# LMQ644_test_SCH.net
KiCad netlist of a schematic drawn in Altium Designer
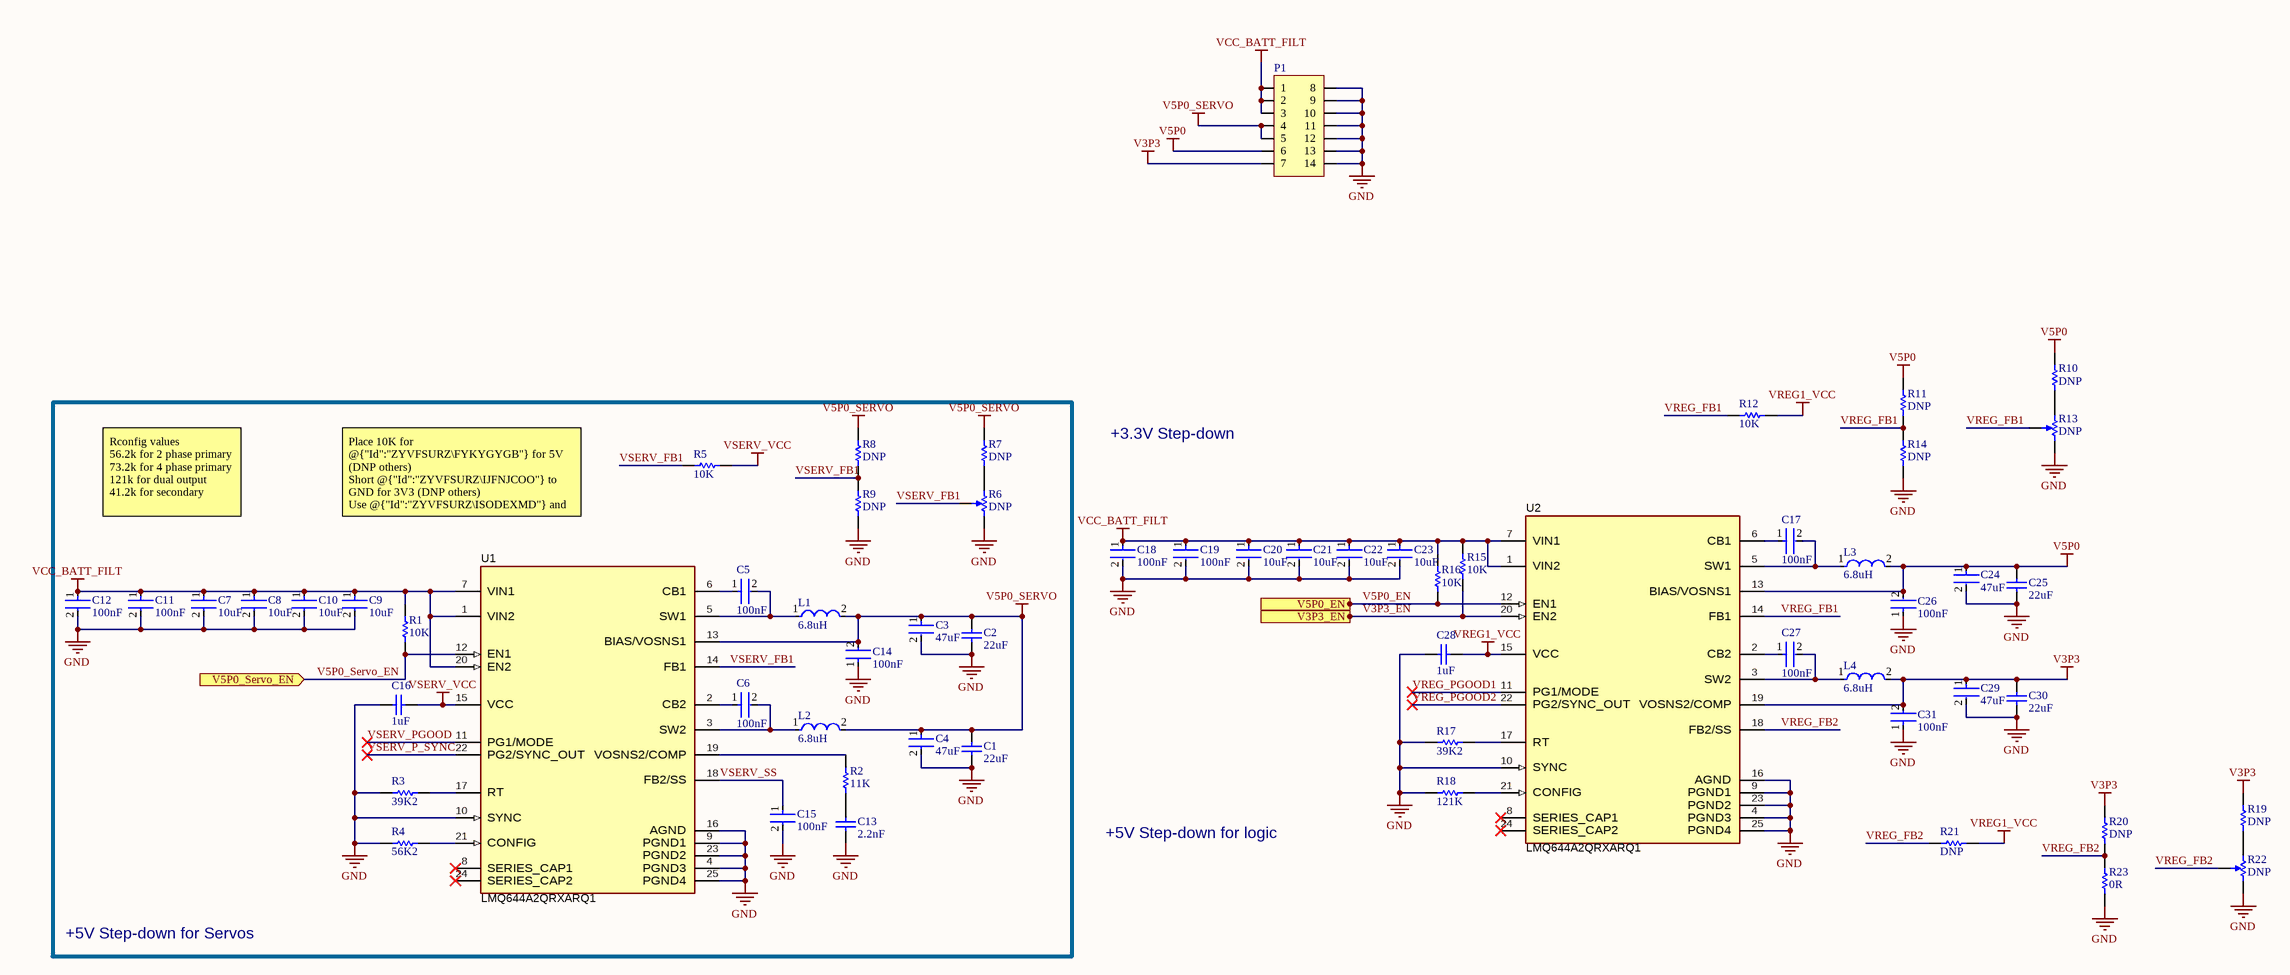
[diagram p0: LMQ644_test_SCH.SchDoc]

(export (version "E")
  (design (tool "Eeschema 10.0.6"))
  (components
    (comp (ref "C1")
      (value "22uF")
      (footprint "CAPC1206(3216)190_L")
      (description "CAP 22uF 6.3V ±20% 1206 (3216 Metric) Thickness 1.9mm SMD")
      (fields (field (name "TOLERANCE") "Â±20%"))
      (libsource (lib "Altium Content Vault") (part "CAP"))
    )
    (comp (ref "C2")
      (value "22uF")
      (footprint "CAPC1206(3216)190_L")
      (description "CAP 22uF 6.3V ±20% 1206 (3216 Metric) Thickness 1.9mm SMD")
      (fields (field (name "TOLERANCE") "Â±20%"))
      (libsource (lib "Altium Content Vault") (part "CAP"))
    )
    (comp (ref "C3")
      (value "47uF")
      (footprint "FP-C3216-160-0_2-MFG")
      (description "Multilayer Ceramic Capacitors 47uF ±20% 16V X5R SMD 1206\r\nC3216X5R1C476M160AB")
      (fields (field (name "TOLERANCE") "20%"))
      (libsource (lib "Altium Content Vault") (part "11868f565c42a9108669ba33697ecf6"))
    )
    (comp (ref "C4")
      (value "47uF")
      (footprint "FP-C3216-160-0_2-MFG")
      (description "Multilayer Ceramic Capacitors 47uF ±20% 16V X5R SMD 1206\r\nC3216X5R1C476M160AB")
      (fields (field (name "TOLERANCE") "20%"))
      (libsource (lib "Altium Content Vault") (part "11868f565c42a9108669ba33697ecf6"))
    )
    (comp (ref "C5")
      (value "100nF")
      (footprint "FP-CGA3E-0_3-0_1-IPC_C")
      (description "Cap Ceramic 100nF 50V X7R 10% Pad SMD 0603 +125°C Automotive T/R\r\nCGA3E2X7R1H104K080AA")
      (fields (field (name "TOLERANCE") "10%") (field (name "VOLTAGE") "50V"))
      (libsource (lib "Altium Content Vault") (part "b4654b650e69147ec39a6b967a45e02"))
    )
    (comp (ref "C6")
      (value "100nF")
      (footprint "FP-CGA3E-0_3-0_1-IPC_C")
      (description "Cap Ceramic 100nF 50V X7R 10% Pad SMD 0603 +125°C Automotive T/R\r\nCGA3E2X7R1H104K080AA")
      (fields (field (name "TOLERANCE") "10%") (field (name "VOLTAGE") "50V"))
      (libsource (lib "Altium Content Vault") (part "b4654b650e69147ec39a6b967a45e02"))
    )
    (comp (ref "C7")
      (value "10uF")
      (footprint "FP-GRM32-MFG")
      (description "CAP CER 10UF 50V X7R 1210")
      (fields (field (name "TOLERANCE") "10%") (field (name "MANUFACTURER PART NUMBER") "GRM32ER71H106KA12L"))
      (libsource (lib "Altium Content Vault") (part "11868f565c42a9108669ba33697ecf6"))
    )
    (comp (ref "C8")
      (value "10uF")
      (footprint "FP-GRM32-MFG")
      (description "CAP CER 10UF 50V X7R 1210")
      (fields (field (name "TOLERANCE") "10%") (field (name "MANUFACTURER PART NUMBER") "GRM32ER71H106KA12L"))
      (libsource (lib "Altium Content Vault") (part "11868f565c42a9108669ba33697ecf6"))
    )
    (comp (ref "C9")
      (value "10uF")
      (footprint "FP-GRM32-MFG")
      (description "CAP CER 10UF 50V X7R 1210")
      (fields (field (name "TOLERANCE") "10%") (field (name "MANUFACTURER PART NUMBER") "GRM32ER71H106KA12L"))
      (libsource (lib "Altium Content Vault") (part "11868f565c42a9108669ba33697ecf6"))
    )
    (comp (ref "C10")
      (value "10uF")
      (footprint "FP-GRM32-MFG")
      (description "CAP CER 10UF 50V X7R 1210")
      (fields (field (name "TOLERANCE") "10%") (field (name "MANUFACTURER PART NUMBER") "GRM32ER71H106KA12L"))
      (libsource (lib "Altium Content Vault") (part "11868f565c42a9108669ba33697ecf6"))
    )
    (comp (ref "C11")
      (value "100nF")
      (footprint "FP-1206-L_3_2_0_2-W_1_6_0-MFG")
      (description "General Purpose Ceramic Capacitor, 1206, 100nF, 20%, X5R, 15%, 25V")
      (fields (field (name "TOLERANCE") "20%"))
      (libsource (lib "Altium Content Vault") (part "02cd4be3c70576c341d710602a673aa"))
    )
    (comp (ref "C12")
      (value "100nF")
      (footprint "FP-1206-L_3_2_0_2-W_1_6_0-MFG")
      (description "General Purpose Ceramic Capacitor, 1206, 100nF, 20%, X5R, 15%, 25V")
      (fields (field (name "TOLERANCE") "20%"))
      (libsource (lib "Altium Content Vault") (part "02cd4be3c70576c341d710602a673aa"))
    )
    (comp (ref "C13")
      (value "2.2nF")
      (footprint "CAPC1608X90X35NL10T15")
      (fields (field (name "MANUFACTURER") "Murata"))
      (libsource (lib "Altium Content Vault") (part "CAP-NP-2"))
    )
    (comp (ref "C14")
      (value "100nF")
      (footprint "FP-CGA3E-0_3-0_1-IPC_C")
      (description "Cap Ceramic 100nF 50V X7R 10% Pad SMD 0603 +125°C Automotive T/R\r\nCGA3E2X7R1H104K080AA")
      (fields (field (name "TOLERANCE") "10%") (field (name "VOLTAGE") "50V"))
      (libsource (lib "Altium Content Vault") (part "b4654b650e69147ec39a6b967a45e02"))
    )
    (comp (ref "C15")
      (value "100nF")
      (footprint "FP-CGA3E-0_3-0_1-IPC_C")
      (description "Cap Ceramic 100nF 50V X7R 10% Pad SMD 0603 +125°C Automotive T/R\r\nCGA3E2X7R1H104K080AA")
      (fields (field (name "TOLERANCE") "10%") (field (name "VOLTAGE") "50V"))
      (libsource (lib "Altium Content Vault") (part "b4654b650e69147ec39a6b967a45e02"))
    )
    (comp (ref "C16")
      (value "1uF")
      (footprint "0603")
      (description "CAP 1uF 25V ±10% 0603 (1608 Metric) Thickness 1mm SMD")
      (fields (field (name "TOLERANCE") "Â±10%"))
      (libsource (lib "TAUV-Lib") (part "1uF 0603"))
    )
    (comp (ref "C17")
      (value "100nF")
      (footprint "FP-CGA3E-0_3-0_1-IPC_C")
      (description "Cap Ceramic 100nF 50V X7R 10% Pad SMD 0603 +125°C Automotive T/R\r\nCGA3E2X7R1H104K080AA")
      (fields (field (name "TOLERANCE") "10%") (field (name "VOLTAGE") "50V"))
      (libsource (lib "Altium Content Vault") (part "b4654b650e69147ec39a6b967a45e02"))
    )
    (comp (ref "C18")
      (value "100nF")
      (footprint "FP-1206-L_3_2_0_2-W_1_6_0-MFG")
      (description "General Purpose Ceramic Capacitor, 1206, 100nF, 20%, X5R, 15%, 25V")
      (fields (field (name "TOLERANCE") "20%"))
      (libsource (lib "Altium Content Vault") (part "02cd4be3c70576c341d710602a673aa"))
    )
    (comp (ref "C19")
      (value "100nF")
      (footprint "FP-1206-L_3_2_0_2-W_1_6_0-MFG")
      (description "General Purpose Ceramic Capacitor, 1206, 100nF, 20%, X5R, 15%, 25V")
      (fields (field (name "TOLERANCE") "20%"))
      (libsource (lib "Altium Content Vault") (part "02cd4be3c70576c341d710602a673aa"))
    )
    (comp (ref "C20")
      (value "10uF")
      (footprint "FP-GRM32-MFG")
      (description "CAP CER 10UF 50V X7R 1210")
      (fields (field (name "TOLERANCE") "10%") (field (name "MANUFACTURER PART NUMBER") "GRM32ER71H106KA12L"))
      (libsource (lib "Altium Content Vault") (part "11868f565c42a9108669ba33697ecf6"))
    )
    (comp (ref "C21")
      (value "10uF")
      (footprint "FP-GRM32-MFG")
      (description "CAP CER 10UF 50V X7R 1210")
      (fields (field (name "TOLERANCE") "10%") (field (name "MANUFACTURER PART NUMBER") "GRM32ER71H106KA12L"))
      (libsource (lib "Altium Content Vault") (part "11868f565c42a9108669ba33697ecf6"))
    )
    (comp (ref "C22")
      (value "10uF")
      (footprint "FP-GRM32-MFG")
      (description "CAP CER 10UF 50V X7R 1210")
      (fields (field (name "TOLERANCE") "10%") (field (name "MANUFACTURER PART NUMBER") "GRM32ER71H106KA12L"))
      (libsource (lib "Altium Content Vault") (part "11868f565c42a9108669ba33697ecf6"))
    )
    (comp (ref "C23")
      (value "10uF")
      (footprint "FP-GRM32-MFG")
      (description "CAP CER 10UF 50V X7R 1210")
      (fields (field (name "TOLERANCE") "10%") (field (name "MANUFACTURER PART NUMBER") "GRM32ER71H106KA12L"))
      (libsource (lib "Altium Content Vault") (part "11868f565c42a9108669ba33697ecf6"))
    )
    (comp (ref "C24")
      (value "47uF")
      (footprint "FP-C3216-160-0_2-MFG")
      (description "Multilayer Ceramic Capacitors 47uF ±20% 16V X5R SMD 1206\r\nC3216X5R1C476M160AB")
      (fields (field (name "TOLERANCE") "20%"))
      (libsource (lib "Altium Content Vault") (part "11868f565c42a9108669ba33697ecf6"))
    )
    (comp (ref "C25")
      (value "22uF")
      (footprint "CAPC1206(3216)190_L")
      (description "CAP 22uF 6.3V ±20% 1206 (3216 Metric) Thickness 1.9mm SMD")
      (fields (field (name "TOLERANCE") "Â±20%"))
      (libsource (lib "Altium Content Vault") (part "CAP"))
    )
    (comp (ref "C26")
      (value "100nF")
      (footprint "FP-CGA3E-0_3-0_1-IPC_C")
      (description "Cap Ceramic 100nF 50V X7R 10% Pad SMD 0603 +125°C Automotive T/R\r\nCGA3E2X7R1H104K080AA")
      (fields (field (name "TOLERANCE") "10%") (field (name "VOLTAGE") "50V"))
      (libsource (lib "Altium Content Vault") (part "b4654b650e69147ec39a6b967a45e02"))
    )
    (comp (ref "C27")
      (value "100nF")
      (footprint "FP-CGA3E-0_3-0_1-IPC_C")
      (description "Cap Ceramic 100nF 50V X7R 10% Pad SMD 0603 +125°C Automotive T/R\r\nCGA3E2X7R1H104K080AA")
      (fields (field (name "TOLERANCE") "10%") (field (name "VOLTAGE") "50V"))
      (libsource (lib "Altium Content Vault") (part "b4654b650e69147ec39a6b967a45e02"))
    )
    (comp (ref "C28")
      (value "1uF")
      (footprint "0603")
      (description "CAP 1uF 25V ±10% 0603 (1608 Metric) Thickness 1mm SMD")
      (fields (field (name "TOLERANCE") "Â±10%"))
      (libsource (lib "TAUV-Lib") (part "1uF 0603"))
    )
    (comp (ref "C29")
      (value "47uF")
      (footprint "FP-C3216-160-0_2-MFG")
      (description "Multilayer Ceramic Capacitors 47uF ±20% 16V X5R SMD 1206\r\nC3216X5R1C476M160AB")
      (fields (field (name "TOLERANCE") "20%"))
      (libsource (lib "Altium Content Vault") (part "11868f565c42a9108669ba33697ecf6"))
    )
    (comp (ref "C30")
      (value "22uF")
      (footprint "CAPC1206(3216)190_L")
      (description "CAP 22uF 6.3V ±20% 1206 (3216 Metric) Thickness 1.9mm SMD")
      (fields (field (name "TOLERANCE") "Â±20%"))
      (libsource (lib "Altium Content Vault") (part "CAP"))
    )
    (comp (ref "C31")
      (value "100nF")
      (footprint "FP-CGA3E-0_3-0_1-IPC_C")
      (description "Cap Ceramic 100nF 50V X7R 10% Pad SMD 0603 +125°C Automotive T/R\r\nCGA3E2X7R1H104K080AA")
      (fields (field (name "TOLERANCE") "10%") (field (name "VOLTAGE") "50V"))
      (libsource (lib "Altium Content Vault") (part "b4654b650e69147ec39a6b967a45e02"))
    )
    (comp (ref "L1")
      (value "6.8uH")
      (footprint "FP-IHLP-4040DZ-FP_3_124x3-MFG")
      (description "Commercial Inductors, High Saturation Series 6.8uH 8A 23.3mΩ 20%\r\nIHLP4040DZER6R8M01")
      (fields (field (name "TOLERANCE") "20%"))
      (libsource (lib "Altium Content Vault") (part "725321dda6339637d4d059423bc1c3c"))
    )
    (comp (ref "L2")
      (value "6.8uH")
      (footprint "FP-IHLP-4040DZ-FP_3_124x3-MFG")
      (description "Commercial Inductors, High Saturation Series 6.8uH 8A 23.3mΩ 20%\r\nIHLP4040DZER6R8M01")
      (fields (field (name "TOLERANCE") "20%"))
      (libsource (lib "Altium Content Vault") (part "725321dda6339637d4d059423bc1c3c"))
    )
    (comp (ref "L3")
      (value "6.8uH")
      (footprint "FP-IHLP-4040DZ-FP_3_124x3-MFG")
      (description "Commercial Inductors, High Saturation Series 6.8uH 8A 23.3mΩ 20%\r\nIHLP4040DZER6R8M01")
      (fields (field (name "TOLERANCE") "20%"))
      (libsource (lib "Altium Content Vault") (part "725321dda6339637d4d059423bc1c3c"))
    )
    (comp (ref "L4")
      (value "6.8uH")
      (footprint "FP-IHLP-4040DZ-FP_3_124x3-MFG")
      (description "Commercial Inductors, High Saturation Series 6.8uH 8A 23.3mΩ 20%\r\nIHLP4040DZER6R8M01")
      (fields (field (name "TOLERANCE") "20%"))
      (libsource (lib "Altium Content Vault") (part "725321dda6339637d4d059423bc1c3c"))
    )
    (comp (ref "P1")
      (value "14-Pin 2-Row Nano-Fit Right Angle")
      (footprint "MOLEX NANO-FIT 2X7 - Right Angle")
      (description "NanoFit Right Hdr TH DR 14Ckt")
      (fields (field (name "PART NUMBER") "105314-1214") (field (name "MANUFACTURER") "Molex"))
      (libsource (lib "TAUV-Lib") (part "14-Pin 2-Row Nano-Fit Right Angle"))
    )
    (comp (ref "R1")
      (value "10K")
      (footprint "0603")
      (description "Chip Resistor, 10 KOhm, +/- 1%, 100 mW, -55 to 155 degC, 0603 (1608 Metric), RoHS, Tape and Reel")
      (fields (field (name "MANUFACTURER") "Vishay Semiconductor"))
      (libsource (lib "TAUV-Lib") (part "10K 0603"))
    )
    (comp (ref "R2")
      (value "11K")
      (footprint "RESC1609X50X30LL10T20")
      (description "CRCW060311K0FKEA\r\n11K 0603")
      (fields (field (name "PART NUMBER") "CRCW060311K0FKEA") (field (name "MANUFACTURER") "Vishay Dale"))
      (libsource (lib "Altium Content Vault") (part "RES"))
    )
    (comp (ref "R3")
      (value "39K2")
      (footprint "RESC1608X55X25LL10T15")
      (description "RC0603FR-0739K2L\r\n0603 39.2k")
      (fields (field (name "PART NUMBER") "RC0603FR-0739K2L") (field (name "MANUFACTURER") "Yageo"))
      (libsource (lib "Altium Content Vault") (part "RES"))
    )
    (comp (ref "R4")
      (value "56K2")
      (footprint "RESC1608X55X25LL10T15")
      (libsource (lib "Altium Content Vault") (part "RES-2"))
    )
    (comp (ref "R5")
      (value "10K")
      (footprint "0603")
      (description "Chip Resistor, 10 KOhm, +/- 1%, 100 mW, -55 to 155 degC, 0603 (1608 Metric), RoHS, Tape and Reel")
      (fields (field (name "MANUFACTURER") "Vishay Semiconductor"))
      (libsource (lib "TAUV-Lib") (part "10K 0603"))
    )
    (comp (ref "R6")
      (value "DNP")
      (footprint "BOUR-TC33X-2_V")
      (description "Trimming Potentiometer, 10000 Ohm, -40 to 100 degC, 3-Pin SMD, RoHS, Tape and Reel\r\nTC33X-2-103E")
      (fields (field (name "TOLERANCE") "25%") (field (name "MANUFACTURER") "Bourns"))
      (libsource (lib "Altium Content Vault") (part "RES-ADJ-3_A"))
    )
    (comp (ref "R7")
      (value "DNP")
      (footprint "0603")
      (description "Chip Resistor, 10 KOhm, +/- 1%, 100 mW, -55 to 155 degC, 0603 (1608 Metric), RoHS, Tape and Reel")
      (fields (field (name "MANUFACTURER") "Vishay Semiconductor"))
      (libsource (lib "TAUV-Lib") (part "10K 0603"))
    )
    (comp (ref "R8")
      (value "DNP")
      (footprint "0603")
      (description "DNP 0603 Resistor")
      (libsource (lib "TAUV-Lib") (part "DNP 0603 R"))
    )
    (comp (ref "R9")
      (value "DNP")
      (footprint "0603")
      (description "DNP 0603 Resistor")
      (libsource (lib "TAUV-Lib") (part "DNP 0603 R"))
    )
    (comp (ref "R10")
      (value "DNP")
      (footprint "0603")
      (description "Chip Resistor, 10 KOhm, +/- 1%, 100 mW, -55 to 155 degC, 0603 (1608 Metric), RoHS, Tape and Reel")
      (fields (field (name "MANUFACTURER") "Vishay Semiconductor"))
      (libsource (lib "TAUV-Lib") (part "10K 0603"))
    )
    (comp (ref "R11")
      (value "DNP")
      (footprint "0603")
      (description "DNP 0603 Resistor")
      (libsource (lib "TAUV-Lib") (part "DNP 0603 R"))
    )
    (comp (ref "R12")
      (value "10K")
      (footprint "0603")
      (description "Chip Resistor, 10 KOhm, +/- 1%, 100 mW, -55 to 155 degC, 0603 (1608 Metric), RoHS, Tape and Reel")
      (fields (field (name "MANUFACTURER") "Vishay Semiconductor"))
      (libsource (lib "TAUV-Lib") (part "10K 0603"))
    )
    (comp (ref "R13")
      (value "DNP")
      (footprint "BOUR-TC33X-2_V")
      (description "Trimming Potentiometer, 10000 Ohm, -40 to 100 degC, 3-Pin SMD, RoHS, Tape and Reel\r\nTC33X-2-103E")
      (fields (field (name "TOLERANCE") "25%") (field (name "MANUFACTURER") "Bourns"))
      (libsource (lib "Altium Content Vault") (part "RES-ADJ-3_A"))
    )
    (comp (ref "R14")
      (value "DNP")
      (footprint "0603")
      (description "DNP 0603 Resistor")
      (libsource (lib "TAUV-Lib") (part "DNP 0603 R"))
    )
    (comp (ref "R15")
      (value "10K")
      (footprint "0603")
      (description "Chip Resistor, 10 KOhm, +/- 1%, 100 mW, -55 to 155 degC, 0603 (1608 Metric), RoHS, Tape and Reel")
      (fields (field (name "MANUFACTURER") "Vishay Semiconductor"))
      (libsource (lib "TAUV-Lib") (part "10K 0603"))
    )
    (comp (ref "R16")
      (value "10K")
      (footprint "0603")
      (description "Chip Resistor, 10 KOhm, +/- 1%, 100 mW, -55 to 155 degC, 0603 (1608 Metric), RoHS, Tape and Reel")
      (fields (field (name "MANUFACTURER") "Vishay Semiconductor"))
      (libsource (lib "TAUV-Lib") (part "10K 0603"))
    )
    (comp (ref "R17")
      (value "39K2")
      (footprint "RESC1608X55X25LL10T15")
      (description "RC0603FR-0739K2L\r\n0603 39.2k")
      (fields (field (name "PART NUMBER") "RC0603FR-0739K2L") (field (name "MANUFACTURER") "Yageo"))
      (libsource (lib "Altium Content Vault") (part "RES"))
    )
    (comp (ref "R18")
      (value "121K")
      (footprint "RESC1608X55X30LL15T15")
      (description "0603 121K\r\nERJ-3EKF1213V")
      (fields (field (name "MANUFACTURER") "Panasonic") (field (name "PART NUMBER") "ERJ-3EKF1213V"))
      (libsource (lib "Altium Content Vault") (part "RES"))
    )
    (comp (ref "R19")
      (value "DNP")
      (footprint "0603")
      (description "Chip Resistor, 10 KOhm, +/- 1%, 100 mW, -55 to 155 degC, 0603 (1608 Metric), RoHS, Tape and Reel")
      (fields (field (name "MANUFACTURER") "Vishay Semiconductor"))
      (libsource (lib "TAUV-Lib") (part "10K 0603"))
    )
    (comp (ref "R20")
      (value "DNP")
      (footprint "0603")
      (description "DNP 0603 Resistor")
      (libsource (lib "TAUV-Lib") (part "DNP 0603 R"))
    )
    (comp (ref "R21")
      (value "DNP")
      (footprint "0603")
      (description "DNP 0603 Resistor")
      (libsource (lib "TAUV-Lib") (part "DNP 0603 R"))
    )
    (comp (ref "R22")
      (value "DNP")
      (footprint "BOUR-TC33X-2_V")
      (description "Trimming Potentiometer, 10000 Ohm, -40 to 100 degC, 3-Pin SMD, RoHS, Tape and Reel\r\nTC33X-2-103E")
      (fields (field (name "TOLERANCE") "25%") (field (name "MANUFACTURER") "Bourns"))
      (libsource (lib "Altium Content Vault") (part "RES-ADJ-3_A"))
    )
    (comp (ref "R23")
      (value "0R")
      (footprint "RESC1608X55X25LL10T15")
      (fields (field (name "TOLERANCE") "5%") (field (name "MANUFACTURER") "Yageo"))
      (libsource (lib "Altium Content Vault") (part "RES-2"))
    )
    (comp (ref "U1")
      (value "LMQ644A2QRXARQ1")
      (footprint "RXA0024A-MFG")
      (description "LMQ644A2-Q1 3-V to 36-V, 12A, Low Iq dual buck converter")
      (fields (field (name "MANUFACTURER") "Texas Instruments") (field (name "PARTNUMBER") "LMQ644A2QRXARQ1"))
      (libsource (lib "TAUV-Lib") (part "SYM-LMQ644A2QRXARQ1"))
    )
    (comp (ref "U2")
      (value "LMQ644A2QRXARQ1")
      (footprint "RXA0024A-MFG")
      (description "LMQ644A2-Q1 3-V to 36-V, 12A, Low Iq dual buck converter")
      (fields (field (name "MANUFACTURER") "Texas Instruments") (field (name "PARTNUMBER") "LMQ644A2QRXARQ1"))
      (libsource (lib "TAUV-Lib") (part "SYM-LMQ644A2QRXARQ1"))
    )
  )
  (nets
    (net (code "1") (name "/V3P3_EN") (class "Default")
      (node (ref "R15") (pin "1") (pinfunction "1_1") (pintype "passive"))
      (node (ref "U2") (pin "20") (pinfunction "EN2_20") (pintype "input"))
    )
    (net (code "2") (name "/V5P0_EN") (class "Default")
      (node (ref "R16") (pin "1") (pinfunction "1_1") (pintype "passive"))
      (node (ref "U2") (pin "12") (pinfunction "EN1_12") (pintype "input"))
    )
    (net (code "3") (name "/V5P0_Servo_EN") (class "Default")
      (node (ref "R1") (pin "1") (pinfunction "1_1") (pintype "passive"))
      (node (ref "U1") (pin "12") (pinfunction "EN1_12") (pintype "input"))
    )
    (net (code "4") (name "/VREG_FB1") (class "Default")
      (node (ref "R11") (pin "2") (pinfunction "2_2") (pintype "passive"))
      (node (ref "R12") (pin "2") (pinfunction "2_2") (pintype "passive"))
      (node (ref "R13") (pin "2") (pinfunction "2_2") (pintype "passive"))
      (node (ref "R14") (pin "1") (pinfunction "1_1") (pintype "passive"))
      (node (ref "U2") (pin "14") (pinfunction "FB1_14") (pintype "passive"))
    )
    (net (code "5") (name "/VREG_FB2") (class "Default")
      (node (ref "R20") (pin "2") (pinfunction "2_2") (pintype "passive"))
      (node (ref "R21") (pin "1") (pinfunction "1_1") (pintype "passive"))
      (node (ref "R22") (pin "2") (pinfunction "2_2") (pintype "passive"))
      (node (ref "R23") (pin "2") (pinfunction "2_2") (pintype "passive"))
      (node (ref "U2") (pin "18") (pinfunction "FB2/SS_18") (pintype "passive"))
    )
    (net (code "6") (name "/VREG_PGOOD1") (class "Default")
      (node (ref "U2") (pin "11") (pinfunction "PG1/MODE_11") (pintype "open_collector+no_connect"))
    )
    (net (code "7") (name "/VREG_PGOOD2") (class "Default")
      (node (ref "U2") (pin "22") (pinfunction "PG2/SYNC_OUT_22") (pintype "open_collector+no_connect"))
    )
    (net (code "8") (name "/VSERV_FB1") (class "Default")
      (node (ref "R5") (pin "2") (pinfunction "2_2") (pintype "passive"))
      (node (ref "R6") (pin "2") (pinfunction "2_2") (pintype "passive"))
      (node (ref "R8") (pin "2") (pinfunction "2_2") (pintype "passive"))
      (node (ref "R9") (pin "1") (pinfunction "1_1") (pintype "passive"))
      (node (ref "U1") (pin "14") (pinfunction "FB1_14") (pintype "passive"))
    )
    (net (code "9") (name "/VSERV_PGOOD") (class "Default")
      (node (ref "U1") (pin "11") (pinfunction "PG1/MODE_11") (pintype "open_collector+no_connect"))
    )
    (net (code "10") (name "/VSERV_P_SYNC") (class "Default")
      (node (ref "U1") (pin "22") (pinfunction "PG2/SYNC_OUT_22") (pintype "open_collector+no_connect"))
    )
    (net (code "11") (name "/VSERV_SS") (class "Default")
      (node (ref "C15") (pin "1") (pinfunction "1_1") (pintype "passive"))
      (node (ref "U1") (pin "18") (pinfunction "FB2/SS_18") (pintype "passive"))
    )
    (net (code "12") (name "GND") (class "Default")
      (node (ref "C1") (pin "1") (pinfunction "1_1") (pintype "passive"))
      (node (ref "C10") (pin "2") (pinfunction "2_2") (pintype "passive"))
      (node (ref "C11") (pin "2") (pinfunction "2_2") (pintype "passive"))
      (node (ref "C12") (pin "2") (pinfunction "2_2") (pintype "passive"))
      (node (ref "C13") (pin "2") (pinfunction "2_2") (pintype "passive"))
      (node (ref "C14") (pin "1") (pinfunction "1_1") (pintype "passive"))
      (node (ref "C15") (pin "2") (pinfunction "2_2") (pintype "passive"))
      (node (ref "C16") (pin "2") (pinfunction "2_2") (pintype "passive"))
      (node (ref "C18") (pin "2") (pinfunction "2_2") (pintype "passive"))
      (node (ref "C19") (pin "2") (pinfunction "2_2") (pintype "passive"))
      (node (ref "C2") (pin "1") (pinfunction "1_1") (pintype "passive"))
      (node (ref "C20") (pin "2") (pinfunction "2_2") (pintype "passive"))
      (node (ref "C21") (pin "2") (pinfunction "2_2") (pintype "passive"))
      (node (ref "C22") (pin "2") (pinfunction "2_2") (pintype "passive"))
      (node (ref "C23") (pin "2") (pinfunction "2_2") (pintype "passive"))
      (node (ref "C24") (pin "2") (pinfunction "2_2") (pintype "passive"))
      (node (ref "C25") (pin "1") (pinfunction "1_1") (pintype "passive"))
      (node (ref "C26") (pin "1") (pinfunction "1_1") (pintype "passive"))
      (node (ref "C28") (pin "2") (pinfunction "2_2") (pintype "passive"))
      (node (ref "C29") (pin "2") (pinfunction "2_2") (pintype "passive"))
      (node (ref "C3") (pin "2") (pinfunction "2_2") (pintype "passive"))
      (node (ref "C30") (pin "1") (pinfunction "1_1") (pintype "passive"))
      (node (ref "C31") (pin "1") (pinfunction "1_1") (pintype "passive"))
      (node (ref "C4") (pin "2") (pinfunction "2_2") (pintype "passive"))
      (node (ref "C7") (pin "2") (pinfunction "2_2") (pintype "passive"))
      (node (ref "C8") (pin "2") (pinfunction "2_2") (pintype "passive"))
      (node (ref "C9") (pin "2") (pinfunction "2_2") (pintype "passive"))
      (node (ref "P1") (pin "10") (pinfunction "10_10") (pintype "passive"))
      (node (ref "P1") (pin "11") (pinfunction "11_11") (pintype "passive"))
      (node (ref "P1") (pin "12") (pinfunction "12_12") (pintype "passive"))
      (node (ref "P1") (pin "13") (pinfunction "13_13") (pintype "passive"))
      (node (ref "P1") (pin "14") (pinfunction "14_14") (pintype "passive"))
      (node (ref "P1") (pin "8") (pinfunction "8_8") (pintype "passive"))
      (node (ref "P1") (pin "9") (pinfunction "9_9") (pintype "passive"))
      (node (ref "R13") (pin "3") (pinfunction "3_3") (pintype "passive"))
      (node (ref "R14") (pin "2") (pinfunction "2_2") (pintype "passive"))
      (node (ref "R17") (pin "1") (pinfunction "1_1") (pintype "passive"))
      (node (ref "R18") (pin "1") (pinfunction "1_1") (pintype "passive"))
      (node (ref "R22") (pin "3") (pinfunction "3_3") (pintype "passive"))
      (node (ref "R23") (pin "1") (pinfunction "1_1") (pintype "passive"))
      (node (ref "R3") (pin "1") (pinfunction "1_1") (pintype "passive"))
      (node (ref "R4") (pin "1") (pinfunction "1_1") (pintype "passive"))
      (node (ref "R6") (pin "3") (pinfunction "3_3") (pintype "passive"))
      (node (ref "R9") (pin "2") (pinfunction "2_2") (pintype "passive"))
      (node (ref "U1") (pin "10") (pinfunction "SYNC_10") (pintype "input"))
      (node (ref "U1") (pin "16") (pinfunction "AGND_16") (pintype "power_in"))
      (node (ref "U1") (pin "23") (pinfunction "PGND2_23") (pintype "power_in"))
      (node (ref "U1") (pin "25") (pinfunction "PGND4_25") (pintype "power_in"))
      (node (ref "U1") (pin "4") (pinfunction "PGND3_4") (pintype "power_in"))
      (node (ref "U1") (pin "9") (pinfunction "PGND1_9") (pintype "power_in"))
      (node (ref "U2") (pin "10") (pinfunction "SYNC_10") (pintype "input"))
      (node (ref "U2") (pin "16") (pinfunction "AGND_16") (pintype "power_in"))
      (node (ref "U2") (pin "23") (pinfunction "PGND2_23") (pintype "power_in"))
      (node (ref "U2") (pin "25") (pinfunction "PGND4_25") (pintype "power_in"))
      (node (ref "U2") (pin "4") (pinfunction "PGND3_4") (pintype "power_in"))
      (node (ref "U2") (pin "9") (pinfunction "PGND1_9") (pintype "power_in"))
    )
    (net (code "13") (name "Net-(C13-Pad1)") (class "Default")
      (node (ref "C13") (pin "1") (pinfunction "1_1") (pintype "passive"))
      (node (ref "R2") (pin "2") (pinfunction "2_2") (pintype "passive"))
    )
    (net (code "14") (name "Net-(R6-Pad1)") (class "Default")
      (node (ref "R6") (pin "1") (pinfunction "1_1") (pintype "passive"))
      (node (ref "R7") (pin "2") (pinfunction "2_2") (pintype "passive"))
    )
    (net (code "15") (name "Net-(R10-Pad2)") (class "Default")
      (node (ref "R10") (pin "2") (pinfunction "2_2") (pintype "passive"))
      (node (ref "R13") (pin "1") (pinfunction "1_1") (pintype "passive"))
    )
    (net (code "16") (name "Net-(R19-Pad2)") (class "Default")
      (node (ref "R19") (pin "2") (pinfunction "2_2") (pintype "passive"))
      (node (ref "R22") (pin "1") (pinfunction "1_1") (pintype "passive"))
    )
    (net (code "17") (name "Net-(U1-CB1)") (class "Default")
      (node (ref "C5") (pin "1") (pinfunction "1_1") (pintype "passive"))
      (node (ref "U1") (pin "6") (pinfunction "CB1_6") (pintype "passive"))
    )
    (net (code "18") (name "Net-(U1-CB2)") (class "Default")
      (node (ref "C6") (pin "1") (pinfunction "1_1") (pintype "passive"))
      (node (ref "U1") (pin "2") (pinfunction "CB2_2") (pintype "passive"))
    )
    (net (code "19") (name "Net-(U1-CONFIG)") (class "Default")
      (node (ref "R4") (pin "2") (pinfunction "2_2") (pintype "passive"))
      (node (ref "U1") (pin "21") (pinfunction "CONFIG_21") (pintype "input"))
    )
    (net (code "20") (name "Net-(U1-RT)") (class "Default")
      (node (ref "R3") (pin "2") (pinfunction "2_2") (pintype "passive"))
      (node (ref "U1") (pin "17") (pinfunction "RT_17") (pintype "passive"))
    )
    (net (code "21") (name "Net-(U1-SW1)") (class "Default")
      (node (ref "C5") (pin "2") (pinfunction "2_2") (pintype "passive"))
      (node (ref "L1") (pin "1") (pinfunction "1_1") (pintype "passive"))
      (node (ref "U1") (pin "5") (pinfunction "SW1_5") (pintype "passive"))
    )
    (net (code "22") (name "Net-(U1-SW2)") (class "Default")
      (node (ref "C6") (pin "2") (pinfunction "2_2") (pintype "passive"))
      (node (ref "L2") (pin "1") (pinfunction "1_1") (pintype "passive"))
      (node (ref "U1") (pin "3") (pinfunction "SW2_3") (pintype "passive"))
    )
    (net (code "23") (name "Net-(U1-VOSNS2{slash}COMP)") (class "Default")
      (node (ref "R2") (pin "1") (pinfunction "1_1") (pintype "passive"))
      (node (ref "U1") (pin "19") (pinfunction "VOSNS2/COMP_19") (pintype "passive"))
    )
    (net (code "24") (name "Net-(U2-CB1)") (class "Default")
      (node (ref "C17") (pin "1") (pinfunction "1_1") (pintype "passive"))
      (node (ref "U2") (pin "6") (pinfunction "CB1_6") (pintype "passive"))
    )
    (net (code "25") (name "Net-(U2-CB2)") (class "Default")
      (node (ref "C27") (pin "1") (pinfunction "1_1") (pintype "passive"))
      (node (ref "U2") (pin "2") (pinfunction "CB2_2") (pintype "passive"))
    )
    (net (code "26") (name "Net-(U2-CONFIG)") (class "Default")
      (node (ref "R18") (pin "2") (pinfunction "2_2") (pintype "passive"))
      (node (ref "U2") (pin "21") (pinfunction "CONFIG_21") (pintype "input"))
    )
    (net (code "27") (name "Net-(U2-RT)") (class "Default")
      (node (ref "R17") (pin "2") (pinfunction "2_2") (pintype "passive"))
      (node (ref "U2") (pin "17") (pinfunction "RT_17") (pintype "passive"))
    )
    (net (code "28") (name "Net-(U2-SW1)") (class "Default")
      (node (ref "C17") (pin "2") (pinfunction "2_2") (pintype "passive"))
      (node (ref "L3") (pin "1") (pinfunction "1_1") (pintype "passive"))
      (node (ref "U2") (pin "5") (pinfunction "SW1_5") (pintype "passive"))
    )
    (net (code "29") (name "Net-(U2-SW2)") (class "Default")
      (node (ref "C27") (pin "2") (pinfunction "2_2") (pintype "passive"))
      (node (ref "L4") (pin "1") (pinfunction "1_1") (pintype "passive"))
      (node (ref "U2") (pin "3") (pinfunction "SW2_3") (pintype "passive"))
    )
    (net (code "30") (name "V3P3") (class "Default")
      (node (ref "C29") (pin "1") (pinfunction "1_1") (pintype "passive"))
      (node (ref "C30") (pin "2") (pinfunction "2_2") (pintype "passive"))
      (node (ref "C31") (pin "2") (pinfunction "2_2") (pintype "passive"))
      (node (ref "L4") (pin "2") (pinfunction "2_2") (pintype "passive"))
      (node (ref "P1") (pin "7") (pinfunction "7_7") (pintype "passive"))
      (node (ref "R19") (pin "1") (pinfunction "1_1") (pintype "passive"))
      (node (ref "R20") (pin "1") (pinfunction "1_1") (pintype "passive"))
      (node (ref "U2") (pin "19") (pinfunction "VOSNS2/COMP_19") (pintype "passive"))
    )
    (net (code "31") (name "V5P0") (class "Default")
      (node (ref "C24") (pin "1") (pinfunction "1_1") (pintype "passive"))
      (node (ref "C25") (pin "2") (pinfunction "2_2") (pintype "passive"))
      (node (ref "C26") (pin "2") (pinfunction "2_2") (pintype "passive"))
      (node (ref "L3") (pin "2") (pinfunction "2_2") (pintype "passive"))
      (node (ref "P1") (pin "6") (pinfunction "6_6") (pintype "passive"))
      (node (ref "R10") (pin "1") (pinfunction "1_1") (pintype "passive"))
      (node (ref "R11") (pin "1") (pinfunction "1_1") (pintype "passive"))
      (node (ref "U2") (pin "13") (pinfunction "BIAS/VOSNS1_13") (pintype "passive"))
    )
    (net (code "32") (name "V5P0_SERVO") (class "Default")
      (node (ref "C1") (pin "2") (pinfunction "2_2") (pintype "passive"))
      (node (ref "C14") (pin "2") (pinfunction "2_2") (pintype "passive"))
      (node (ref "C2") (pin "2") (pinfunction "2_2") (pintype "passive"))
      (node (ref "C3") (pin "1") (pinfunction "1_1") (pintype "passive"))
      (node (ref "C4") (pin "1") (pinfunction "1_1") (pintype "passive"))
      (node (ref "L1") (pin "2") (pinfunction "2_2") (pintype "passive"))
      (node (ref "L2") (pin "2") (pinfunction "2_2") (pintype "passive"))
      (node (ref "P1") (pin "4") (pinfunction "4_4") (pintype "passive"))
      (node (ref "P1") (pin "5") (pinfunction "5_5") (pintype "passive"))
      (node (ref "R7") (pin "1") (pinfunction "1_1") (pintype "passive"))
      (node (ref "R8") (pin "1") (pinfunction "1_1") (pintype "passive"))
      (node (ref "U1") (pin "13") (pinfunction "BIAS/VOSNS1_13") (pintype "passive"))
    )
    (net (code "33") (name "VCC_BATT_FILT") (class "Default")
      (node (ref "C10") (pin "1") (pinfunction "1_1") (pintype "passive"))
      (node (ref "C11") (pin "1") (pinfunction "1_1") (pintype "passive"))
      (node (ref "C12") (pin "1") (pinfunction "1_1") (pintype "passive"))
      (node (ref "C18") (pin "1") (pinfunction "1_1") (pintype "passive"))
      (node (ref "C19") (pin "1") (pinfunction "1_1") (pintype "passive"))
      (node (ref "C20") (pin "1") (pinfunction "1_1") (pintype "passive"))
      (node (ref "C21") (pin "1") (pinfunction "1_1") (pintype "passive"))
      (node (ref "C22") (pin "1") (pinfunction "1_1") (pintype "passive"))
      (node (ref "C23") (pin "1") (pinfunction "1_1") (pintype "passive"))
      (node (ref "C7") (pin "1") (pinfunction "1_1") (pintype "passive"))
      (node (ref "C8") (pin "1") (pinfunction "1_1") (pintype "passive"))
      (node (ref "C9") (pin "1") (pinfunction "1_1") (pintype "passive"))
      (node (ref "P1") (pin "1") (pinfunction "1_1") (pintype "passive"))
      (node (ref "P1") (pin "2") (pinfunction "2_2") (pintype "passive"))
      (node (ref "P1") (pin "3") (pinfunction "3_3") (pintype "passive"))
      (node (ref "R1") (pin "2") (pinfunction "2_2") (pintype "passive"))
      (node (ref "R15") (pin "2") (pinfunction "2_2") (pintype "passive"))
      (node (ref "R16") (pin "2") (pinfunction "2_2") (pintype "passive"))
      (node (ref "U1") (pin "1") (pinfunction "VIN2_1") (pintype "power_in"))
      (node (ref "U1") (pin "20") (pinfunction "EN2_20") (pintype "input"))
      (node (ref "U1") (pin "7") (pinfunction "VIN1_7") (pintype "power_in"))
      (node (ref "U2") (pin "1") (pinfunction "VIN2_1") (pintype "power_in"))
      (node (ref "U2") (pin "7") (pinfunction "VIN1_7") (pintype "power_in"))
    )
    (net (code "34") (name "VREG1_VCC") (class "Default")
      (node (ref "C28") (pin "1") (pinfunction "1_1") (pintype "passive"))
      (node (ref "R12") (pin "1") (pinfunction "1_1") (pintype "passive"))
      (node (ref "R21") (pin "2") (pinfunction "2_2") (pintype "passive"))
      (node (ref "U2") (pin "15") (pinfunction "VCC_15") (pintype "passive"))
    )
    (net (code "35") (name "VSERV_VCC") (class "Default")
      (node (ref "C16") (pin "1") (pinfunction "1_1") (pintype "passive"))
      (node (ref "R5") (pin "1") (pinfunction "1_1") (pintype "passive"))
      (node (ref "U1") (pin "15") (pinfunction "VCC_15") (pintype "passive"))
    )
    (net (code "36") (name "unconnected-(U1-SERIES_CAP1-Pad8)") (class "Default")
      (node (ref "U1") (pin "8") (pinfunction "SERIES_CAP1_8") (pintype "passive+no_connect"))
    )
    (net (code "37") (name "unconnected-(U1-SERIES_CAP2-Pad24)") (class "Default")
      (node (ref "U1") (pin "24") (pinfunction "SERIES_CAP2_24") (pintype "passive+no_connect"))
    )
    (net (code "38") (name "unconnected-(U2-SERIES_CAP1-Pad8)") (class "Default")
      (node (ref "U2") (pin "8") (pinfunction "SERIES_CAP1_8") (pintype "passive+no_connect"))
    )
    (net (code "39") (name "unconnected-(U2-SERIES_CAP2-Pad24)") (class "Default")
      (node (ref "U2") (pin "24") (pinfunction "SERIES_CAP2_24") (pintype "passive+no_connect"))
    )
  )
)
